# LM34_LCD_SHIELD.net
KiCad netlist of a schematic drawn in EAGLE
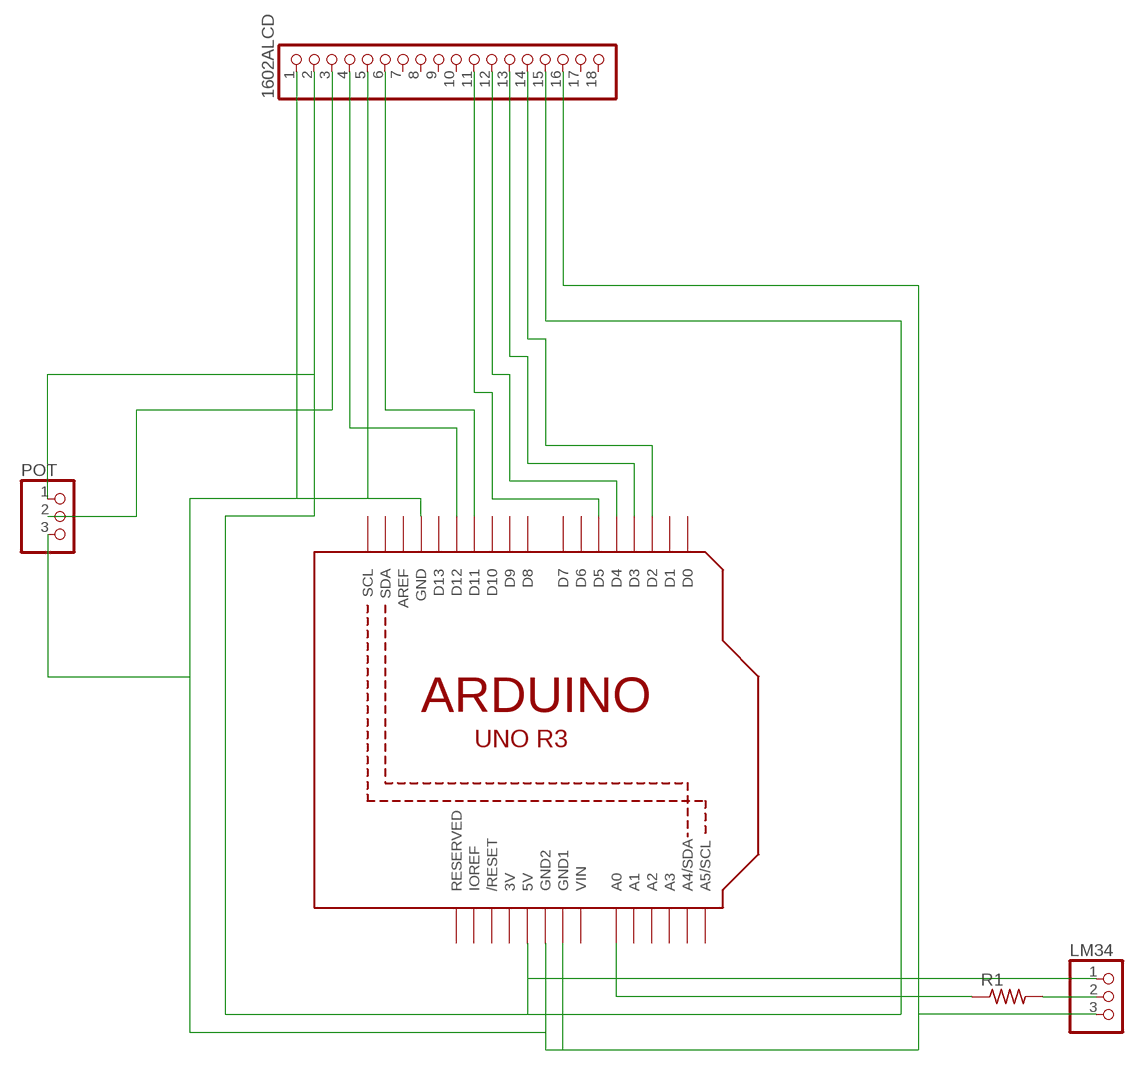
[diagram p0: schematic, sheet 1]

(export (version "E")
  (design (tool "Eeschema 10.0.6"))
  (components
    (comp (ref "1602ALCD")
      (value "PINHD-1X18")
      (footprint "eagle-import:1X18")
      (libsource (lib "eagle-import") (part "PINHD-1X18"))
    )
    (comp (ref "LM34")
      (value "PINHD-1X3CB")
      (footprint "eagle-import:1X03-CLEANBIG")
      (libsource (lib "eagle-import") (part "PINHD-1X3CB"))
    )
    (comp (ref "POT")
      (value "PINHD-1X3CB")
      (footprint "eagle-import:1X03-CLEANBIG")
      (libsource (lib "eagle-import") (part "PINHD-1X3CB"))
    )
    (comp (ref "R1")
      (value "R-US_0207/5V")
      (footprint "eagle-import:0207_5V")
      (libsource (lib "eagle-import") (part "R-US_0207/5V"))
    )
    (comp (ref "U1")
      (value "ARDUINOR3-BPLACE")
      (footprint "eagle-import:ARDUINOR3-BPLACE")
      (libsource (lib "eagle-import") (part "ARDUINOR3-BPLACE"))
    )
  )
  (nets
    (net (code "1") (name "/3V") (class "Default")
      (node (ref "U1") (pin "3V") (pinfunction "3V_3V") (pintype "power_in"))
    )
    (net (code "2") (name "/VIN") (class "Default")
      (node (ref "U1") (pin "VIN") (pinfunction "VIN_VIN") (pintype "power_in"))
    )
    (net (code "3") (name "Net-(1602ALCD-Pad1)") (class "Default")
      (node (ref "1602ALCD") (pin "1") (pinfunction "1_1") (pintype "passive"))
      (node (ref "1602ALCD") (pin "16") (pinfunction "16_16") (pintype "passive"))
      (node (ref "1602ALCD") (pin "5") (pinfunction "5_5") (pintype "passive"))
      (node (ref "LM34") (pin "3") (pinfunction "3_3") (pintype "passive"))
      (node (ref "POT") (pin "3") (pinfunction "3_3") (pintype "passive"))
      (node (ref "U1") (pin "GND") (pinfunction "GND_GND") (pintype "power_in"))
      (node (ref "U1") (pin "GND1") (pinfunction "GND1_GND1") (pintype "power_in"))
      (node (ref "U1") (pin "GND2") (pinfunction "GND2_GND2") (pintype "power_in"))
    )
    (net (code "4") (name "Net-(1602ALCD-Pad3)") (class "Default")
      (node (ref "1602ALCD") (pin "3") (pinfunction "3_3") (pintype "passive"))
      (node (ref "POT") (pin "2") (pinfunction "2_2") (pintype "passive"))
    )
    (net (code "5") (name "Net-(1602ALCD-Pad4)") (class "Default")
      (node (ref "1602ALCD") (pin "4") (pinfunction "4_4") (pintype "passive"))
      (node (ref "U1") (pin "D12") (pinfunction "D12_D12") (pintype "bidirectional"))
    )
    (net (code "6") (name "Net-(1602ALCD-Pad6)") (class "Default")
      (node (ref "1602ALCD") (pin "6") (pinfunction "6_6") (pintype "passive"))
      (node (ref "U1") (pin "D11") (pinfunction "D11_D11") (pintype "bidirectional"))
    )
    (net (code "7") (name "Net-(1602ALCD-Pad11)") (class "Default")
      (node (ref "1602ALCD") (pin "11") (pinfunction "11_11") (pintype "passive"))
      (node (ref "U1") (pin "D5") (pinfunction "D5_D5") (pintype "bidirectional"))
    )
    (net (code "8") (name "Net-(1602ALCD-Pad12)") (class "Default")
      (node (ref "1602ALCD") (pin "12") (pinfunction "12_12") (pintype "passive"))
      (node (ref "U1") (pin "D4") (pinfunction "D4_D4") (pintype "bidirectional"))
    )
    (net (code "9") (name "Net-(1602ALCD-Pad13)") (class "Default")
      (node (ref "1602ALCD") (pin "13") (pinfunction "13_13") (pintype "passive"))
      (node (ref "U1") (pin "D3") (pinfunction "D3_D3") (pintype "bidirectional"))
    )
    (net (code "10") (name "Net-(1602ALCD-Pad14)") (class "Default")
      (node (ref "1602ALCD") (pin "14") (pinfunction "14_14") (pintype "passive"))
      (node (ref "U1") (pin "D2") (pinfunction "D2_D2") (pintype "bidirectional"))
    )
    (net (code "11") (name "Net-(1602ALCD-Pad15)") (class "Default")
      (node (ref "1602ALCD") (pin "15") (pinfunction "15_15") (pintype "passive"))
      (node (ref "1602ALCD") (pin "2") (pinfunction "2_2") (pintype "passive"))
      (node (ref "LM34") (pin "1") (pinfunction "1_1") (pintype "passive"))
      (node (ref "POT") (pin "1") (pinfunction "1_1") (pintype "passive"))
      (node (ref "U1") (pin "5V") (pinfunction "5V_5V") (pintype "power_in"))
    )
    (net (code "12") (name "Net-(LM34-Pad2)") (class "Default")
      (node (ref "LM34") (pin "2") (pinfunction "2_2") (pintype "passive"))
      (node (ref "R1") (pin "2") (pinfunction "2_2") (pintype "passive"))
    )
    (net (code "13") (name "Net-(R1-Pad1)") (class "Default")
      (node (ref "R1") (pin "1") (pinfunction "1_1") (pintype "passive"))
      (node (ref "U1") (pin "A0") (pinfunction "A0_A0") (pintype "bidirectional"))
    )
    (net (code "14") (name "unconnected-(1602ALCD-Pad7)") (class "Default")
      (node (ref "1602ALCD") (pin "7") (pinfunction "7_7") (pintype "passive"))
    )
    (net (code "15") (name "unconnected-(1602ALCD-Pad8)") (class "Default")
      (node (ref "1602ALCD") (pin "8") (pinfunction "8_8") (pintype "passive"))
    )
    (net (code "16") (name "unconnected-(1602ALCD-Pad9)") (class "Default")
      (node (ref "1602ALCD") (pin "9") (pinfunction "9_9") (pintype "passive"))
    )
    (net (code "17") (name "unconnected-(1602ALCD-Pad10)") (class "Default")
      (node (ref "1602ALCD") (pin "10") (pinfunction "10_10") (pintype "passive"))
    )
    (net (code "18") (name "unconnected-(1602ALCD-Pad17)") (class "Default")
      (node (ref "1602ALCD") (pin "17") (pinfunction "17_17") (pintype "passive"))
    )
    (net (code "19") (name "unconnected-(1602ALCD-Pad18)") (class "Default")
      (node (ref "1602ALCD") (pin "18") (pinfunction "18_18") (pintype "passive"))
    )
    (net (code "20") (name "unconnected-(U1-A4{slash}SDA-PadA4)") (class "Default")
      (node (ref "U1") (pin "A4") (pinfunction "A4/SDA_A4") (pintype "bidirectional"))
    )
    (net (code "21") (name "unconnected-(U1-A5{slash}SCL-PadA5)") (class "Default")
      (node (ref "U1") (pin "A5") (pinfunction "A5/SCL_A5") (pintype "bidirectional"))
    )
    (net (code "22") (name "unconnected-(U1-PadA1)") (class "Default")
      (node (ref "U1") (pin "A1") (pinfunction "A1_A1") (pintype "bidirectional"))
    )
    (net (code "23") (name "unconnected-(U1-PadA2)") (class "Default")
      (node (ref "U1") (pin "A2") (pinfunction "A2_A2") (pintype "bidirectional"))
    )
    (net (code "24") (name "unconnected-(U1-PadA3)") (class "Default")
      (node (ref "U1") (pin "A3") (pinfunction "A3_A3") (pintype "bidirectional"))
    )
    (net (code "25") (name "unconnected-(U1-PadAREF)") (class "Default")
      (node (ref "U1") (pin "AREF") (pinfunction "AREF_AREF") (pintype "bidirectional"))
    )
    (net (code "26") (name "unconnected-(U1-PadD0)") (class "Default")
      (node (ref "U1") (pin "D0") (pinfunction "D0_D0") (pintype "bidirectional"))
    )
    (net (code "27") (name "unconnected-(U1-PadD1)") (class "Default")
      (node (ref "U1") (pin "D1") (pinfunction "D1_D1") (pintype "bidirectional"))
    )
    (net (code "28") (name "unconnected-(U1-PadD6)") (class "Default")
      (node (ref "U1") (pin "D6") (pinfunction "D6_D6") (pintype "bidirectional"))
    )
    (net (code "29") (name "unconnected-(U1-PadD7)") (class "Default")
      (node (ref "U1") (pin "D7") (pinfunction "D7_D7") (pintype "bidirectional"))
    )
    (net (code "30") (name "unconnected-(U1-PadD8)") (class "Default")
      (node (ref "U1") (pin "D8") (pinfunction "D8_D8") (pintype "bidirectional"))
    )
    (net (code "31") (name "unconnected-(U1-PadD9)") (class "Default")
      (node (ref "U1") (pin "D9") (pinfunction "D9_D9") (pintype "bidirectional"))
    )
    (net (code "32") (name "unconnected-(U1-PadD10)") (class "Default")
      (node (ref "U1") (pin "D10") (pinfunction "D10_D10") (pintype "bidirectional"))
    )
    (net (code "33") (name "unconnected-(U1-PadD13)") (class "Default")
      (node (ref "U1") (pin "D13") (pinfunction "D13_D13") (pintype "bidirectional"))
    )
    (net (code "34") (name "unconnected-(U1-PadIOREF)") (class "Default")
      (node (ref "U1") (pin "IOREF") (pinfunction "IOREF_IOREF") (pintype "output"))
    )
    (net (code "35") (name "unconnected-(U1-PadRESERVED)") (class "Default")
      (node (ref "U1") (pin "RESERVED") (pinfunction "RESERVED_RESERVED") (pintype "no_connect"))
    )
    (net (code "36") (name "unconnected-(U1-PadSCL)") (class "Default")
      (node (ref "U1") (pin "SCL") (pinfunction "SCL_SCL") (pintype "bidirectional"))
    )
    (net (code "37") (name "unconnected-(U1-PadSDA)") (class "Default")
      (node (ref "U1") (pin "SDA") (pinfunction "SDA_SDA") (pintype "bidirectional"))
    )
    (net (code "38") (name "unconnected-(U1-{slash}RESET-PadRESET)") (class "Default")
      (node (ref "U1") (pin "RESET") (pinfunction "/RESET_RESET") (pintype "bidirectional"))
    )
  )
)
